# Pair_2.net
KiCad netlist of a schematic drawn in Altium Designer
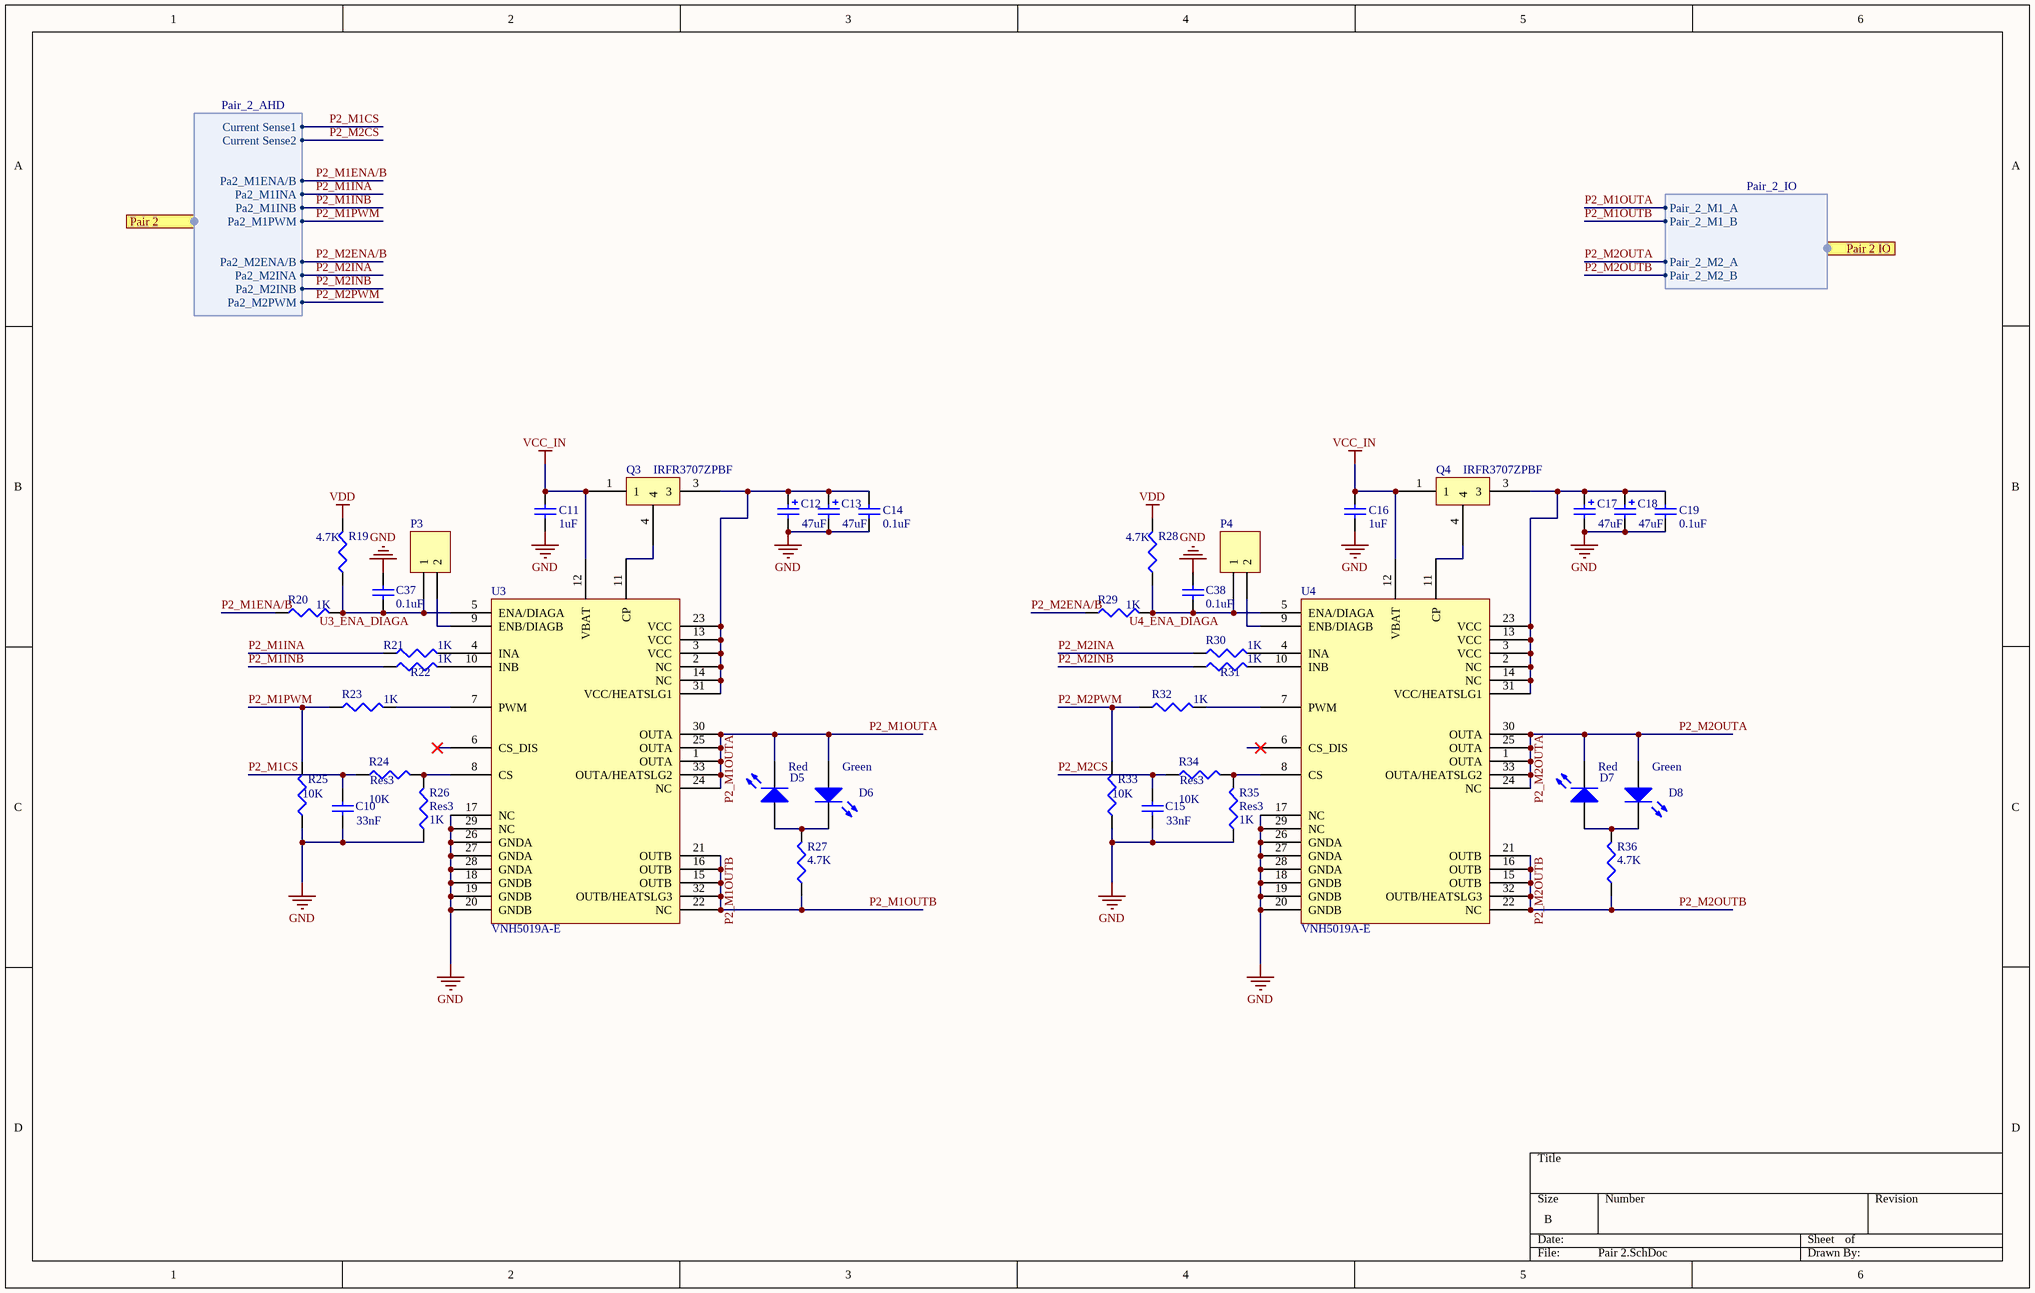
[diagram p0: Pair 2.SchDoc]

(export (version "E")
  (design (tool "Eeschema 10.0.6"))
  (components
    (comp (ref "C10")
      (value "33nF")
      (footprint "1608[0603]")
      (description "Capacitor (Semiconductor SIM Model)")
      (fields (field (name "Comment") "Cap Semi") (field (name "PUBLISHER") "Altium Limited"))
      (libsource (lib "Miscellaneous Devices") (part "Cap Semi"))
    )
    (comp (ref "C11")
      (value "1uF")
      (footprint "1608[0603]")
      (description "Capacitor (Semiconductor SIM Model)")
      (fields (field (name "Comment") "Cap Semi") (field (name "PUBLISHER") "Altium Limited"))
      (libsource (lib "Miscellaneous Devices") (part "Cap Semi"))
    )
    (comp (ref "C12")
      (value "47uF")
      (footprint "CAPPR2-5x6.8")
      (description "Polarized Capacitor (Axial)")
      (fields (field (name "Comment") "Cap Pol2") (field (name "PUBLISHER") "Altium Limited"))
      (libsource (lib "Miscellaneous Devices") (part "Cap Pol2"))
    )
    (comp (ref "C13")
      (value "47uF")
      (footprint "CAPPR2-5x6.8")
      (description "Polarized Capacitor (Axial)")
      (fields (field (name "Comment") "Cap Pol2") (field (name "PUBLISHER") "Altium Limited"))
      (libsource (lib "Miscellaneous Devices") (part "Cap Pol2"))
    )
    (comp (ref "C14")
      (value "0.1uF")
      (footprint "C1206")
      (description "Capacitor (Semiconductor SIM Model)")
      (fields (field (name "Comment") "Cap Semi") (field (name "PUBLISHER") "Altium Limited"))
      (libsource (lib "Miscellaneous Devices") (part "Cap Semi"))
    )
    (comp (ref "C15")
      (value "33nF")
      (footprint "1608[0603]")
      (description "Capacitor (Semiconductor SIM Model)")
      (fields (field (name "Comment") "Cap Semi") (field (name "PUBLISHER") "Altium Limited"))
      (libsource (lib "Miscellaneous Devices") (part "Cap Semi"))
    )
    (comp (ref "C16")
      (value "1uF")
      (footprint "1608[0603]")
      (description "Capacitor (Semiconductor SIM Model)")
      (fields (field (name "Comment") "Cap Semi") (field (name "PUBLISHER") "Altium Limited"))
      (libsource (lib "Miscellaneous Devices") (part "Cap Semi"))
    )
    (comp (ref "C17")
      (value "47uF")
      (footprint "CAPPR2-5x6.8")
      (description "Polarized Capacitor (Axial)")
      (fields (field (name "Comment") "Cap Pol2") (field (name "PUBLISHER") "Altium Limited"))
      (libsource (lib "Miscellaneous Devices") (part "Cap Pol2"))
    )
    (comp (ref "C18")
      (value "47uF")
      (footprint "CAPPR2-5x6.8")
      (description "Polarized Capacitor (Axial)")
      (fields (field (name "Comment") "Cap Pol2") (field (name "PUBLISHER") "Altium Limited"))
      (libsource (lib "Miscellaneous Devices") (part "Cap Pol2"))
    )
    (comp (ref "C19")
      (value "0.1uF")
      (footprint "C1206")
      (description "Capacitor (Semiconductor SIM Model)")
      (fields (field (name "Comment") "Cap Semi") (field (name "PUBLISHER") "Altium Limited"))
      (libsource (lib "Miscellaneous Devices") (part "Cap Semi"))
    )
    (comp (ref "C37")
      (value "0.1uF")
      (footprint "1608[0603]")
      (description "Capacitor (Semiconductor SIM Model)")
      (fields (field (name "Comment") "Cap Semi") (field (name "PUBLISHER") "Altium Limited"))
      (libsource (lib "Miscellaneous Devices") (part "Cap Semi"))
    )
    (comp (ref "C38")
      (value "0.1uF")
      (footprint "1608[0603]")
      (description "Capacitor (Semiconductor SIM Model)")
      (fields (field (name "Comment") "Cap Semi") (field (name "PUBLISHER") "Altium Limited"))
      (libsource (lib "Miscellaneous Devices") (part "Cap Semi"))
    )
    (comp (ref "D5")
      (value "LED2")
      (footprint "3.2X1.6X1.1")
      (description "Typical RED, GREEN, YELLOW, AMBER GaAs LED")
      (fields (field (name "PUBLISHER") "Altium Limited"))
      (libsource (lib "Miscellaneous Devices") (part "LED2"))
    )
    (comp (ref "D6")
      (value "LED2")
      (footprint "3.2X1.6X1.1")
      (description "Typical RED, GREEN, YELLOW, AMBER GaAs LED")
      (fields (field (name "PUBLISHER") "Altium Limited"))
      (libsource (lib "Miscellaneous Devices") (part "LED2"))
    )
    (comp (ref "D7")
      (value "LED2")
      (footprint "3.2X1.6X1.1")
      (description "Typical RED, GREEN, YELLOW, AMBER GaAs LED")
      (fields (field (name "PUBLISHER") "Altium Limited"))
      (libsource (lib "Miscellaneous Devices") (part "LED2"))
    )
    (comp (ref "D8")
      (value "LED2")
      (footprint "3.2X1.6X1.1")
      (description "Typical RED, GREEN, YELLOW, AMBER GaAs LED")
      (fields (field (name "PUBLISHER") "Altium Limited"))
      (libsource (lib "Miscellaneous Devices") (part "LED2"))
    )
    (comp (ref "P3")
      (value "Header 2")
      (footprint "HDR1X2")
      (description "Header, 2-Pin")
      (fields (field (name "PUBLISHER") "Altium Limited"))
      (libsource (lib "Miscellaneous Connectors") (part "Header 2"))
    )
    (comp (ref "P4")
      (value "Header 2")
      (footprint "HDR1X2")
      (description "Header, 2-Pin")
      (fields (field (name "PUBLISHER") "Altium Limited"))
      (libsource (lib "Miscellaneous Connectors") (part "Header 2"))
    )
    (comp (ref "Q3")
      (value "IRFR3707ZPBF")
      (footprint "IRFR3707ZPBF")
      (description "Power FET")
      (libsource (lib "Thruster Shield Part Library") (part "IRFR3707ZPBF"))
    )
    (comp (ref "Q4")
      (value "IRFR3707ZPBF")
      (footprint "IRFR3707ZPBF")
      (description "Power FET")
      (libsource (lib "Thruster Shield Part Library") (part "IRFR3707ZPBF"))
    )
    (comp (ref "R19")
      (value "4.7K")
      (footprint "RESC1608L")
      (description "Resistor")
      (fields (field (name "Comment") "Res3") (field (name "PUBLISHER") "Altium Limited"))
      (libsource (lib "Miscellaneous Devices") (part "Res3"))
    )
    (comp (ref "R20")
      (value "1K")
      (footprint "RESC1608L")
      (description "Resistor")
      (fields (field (name "Comment") "Res3") (field (name "PUBLISHER") "Altium Limited"))
      (libsource (lib "Miscellaneous Devices") (part "Res3"))
    )
    (comp (ref "R21")
      (value "1K")
      (footprint "RESC1608L")
      (description "Resistor")
      (fields (field (name "Comment") "Res3") (field (name "PUBLISHER") "Altium Limited"))
      (libsource (lib "Miscellaneous Devices") (part "Res3"))
    )
    (comp (ref "R22")
      (value "1K")
      (footprint "RESC1608L")
      (description "Resistor")
      (fields (field (name "Comment") "Res3") (field (name "PUBLISHER") "Altium Limited"))
      (libsource (lib "Miscellaneous Devices") (part "Res3"))
    )
    (comp (ref "R23")
      (value "1K")
      (footprint "RESC1608L")
      (description "Resistor")
      (fields (field (name "Comment") "Res3") (field (name "PUBLISHER") "Altium Limited"))
      (libsource (lib "Miscellaneous Devices") (part "Res3"))
    )
    (comp (ref "R24")
      (value "Res3")
      (footprint "RESC1608L")
      (description "Resistor")
      (fields (field (name "ALTIUM_VALUE") "10K") (field (name "PUBLISHER") "Altium Limited"))
      (libsource (lib "Miscellaneous Devices") (part "Res3"))
    )
    (comp (ref "R25")
      (value "10K")
      (footprint "RESC1608L")
      (description "Resistor")
      (fields (field (name "Comment") "Res3") (field (name "PUBLISHER") "Altium Limited"))
      (libsource (lib "Miscellaneous Devices") (part "Res3"))
    )
    (comp (ref "R26")
      (value "Res3")
      (footprint "RESC1608L")
      (description "Resistor")
      (fields (field (name "ALTIUM_VALUE") "1K") (field (name "PUBLISHER") "Altium Limited"))
      (libsource (lib "Miscellaneous Devices") (part "Res3"))
    )
    (comp (ref "R27")
      (value "4.7K")
      (footprint "0805 SMD Resistor")
      (description "Resistor")
      (fields (field (name "Comment") "Res3") (field (name "PUBLISHER") "Altium Limited"))
      (libsource (lib "Miscellaneous Devices") (part "Res3"))
    )
    (comp (ref "R28")
      (value "4.7K")
      (footprint "RESC1608L")
      (description "Resistor")
      (fields (field (name "Comment") "Res3") (field (name "PUBLISHER") "Altium Limited"))
      (libsource (lib "Miscellaneous Devices") (part "Res3"))
    )
    (comp (ref "R29")
      (value "1K")
      (footprint "RESC1608L")
      (description "Resistor")
      (fields (field (name "Comment") "Res3") (field (name "PUBLISHER") "Altium Limited"))
      (libsource (lib "Miscellaneous Devices") (part "Res3"))
    )
    (comp (ref "R30")
      (value "1K")
      (footprint "RESC1608L")
      (description "Resistor")
      (fields (field (name "Comment") "Res3") (field (name "PUBLISHER") "Altium Limited"))
      (libsource (lib "Miscellaneous Devices") (part "Res3"))
    )
    (comp (ref "R31")
      (value "1K")
      (footprint "RESC1608L")
      (description "Resistor")
      (fields (field (name "Comment") "Res3") (field (name "PUBLISHER") "Altium Limited"))
      (libsource (lib "Miscellaneous Devices") (part "Res3"))
    )
    (comp (ref "R32")
      (value "1K")
      (footprint "RESC1608L")
      (description "Resistor")
      (fields (field (name "Comment") "Res3") (field (name "PUBLISHER") "Altium Limited"))
      (libsource (lib "Miscellaneous Devices") (part "Res3"))
    )
    (comp (ref "R33")
      (value "10K")
      (footprint "RESC1608L")
      (description "Resistor")
      (fields (field (name "Comment") "Res3") (field (name "PUBLISHER") "Altium Limited"))
      (libsource (lib "Miscellaneous Devices") (part "Res3"))
    )
    (comp (ref "R34")
      (value "Res3")
      (footprint "RESC1608L")
      (description "Resistor")
      (fields (field (name "ALTIUM_VALUE") "10K") (field (name "PUBLISHER") "Altium Limited"))
      (libsource (lib "Miscellaneous Devices") (part "Res3"))
    )
    (comp (ref "R35")
      (value "Res3")
      (footprint "RESC1608L")
      (description "Resistor")
      (fields (field (name "ALTIUM_VALUE") "1K") (field (name "PUBLISHER") "Altium Limited"))
      (libsource (lib "Miscellaneous Devices") (part "Res3"))
    )
    (comp (ref "R36")
      (value "4.7K")
      (footprint "0805 SMD Resistor")
      (description "Resistor")
      (fields (field (name "Comment") "Res3") (field (name "PUBLISHER") "Altium Limited"))
      (libsource (lib "Miscellaneous Devices") (part "Res3"))
    )
    (comp (ref "U3")
      (value "VNH5019A-E")
      (footprint "VNH5019A-E")
      (description "VNH5019A-E H-Bridge")
      (libsource (lib "Thruster Shield Part Library") (part "VNH5019A-E"))
    )
    (comp (ref "U4")
      (value "VNH5019A-E")
      (footprint "VNH5019A-E")
      (description "VNH5019A-E H-Bridge")
      (libsource (lib "Thruster Shield Part Library") (part "VNH5019A-E"))
    )
  )
  (nets
    (net (code "3") (name "/P2_M1CS") (class "Default")
      (node (ref "C10") (pin "2") (pinfunction "2_2") (pintype "passive"))
      (node (ref "R24") (pin "1") (pinfunction "1_1") (pintype "passive"))
    )
    (net (code "4") (name "/P2_M1ENA{slash}B") (class "Default")
      (node (ref "R20") (pin "1") (pinfunction "1_1") (pintype "passive"))
    )
    (net (code "5") (name "/P2_M1INA") (class "Default")
      (node (ref "R21") (pin "1") (pinfunction "1_1") (pintype "passive"))
    )
    (net (code "6") (name "/P2_M1INB") (class "Default")
      (node (ref "R22") (pin "1") (pinfunction "1_1") (pintype "passive"))
    )
    (net (code "7") (name "/P2_M1OUTA") (class "Default")
      (node (ref "D5") (pin "2") (pinfunction "K_2") (pintype "passive"))
      (node (ref "D6") (pin "1") (pinfunction "A_1") (pintype "passive"))
      (node (ref "U3") (pin "1") (pinfunction "OUTA_1") (pintype "passive"))
      (node (ref "U3") (pin "24") (pinfunction "NC_24") (pintype "passive"))
      (node (ref "U3") (pin "25") (pinfunction "OUTA_25") (pintype "passive"))
      (node (ref "U3") (pin "30") (pinfunction "OUTA_30") (pintype "passive"))
      (node (ref "U3") (pin "33") (pinfunction "OUTA/HEATSLG2_33") (pintype "passive"))
    )
    (net (code "8") (name "/P2_M1OUTB") (class "Default")
      (node (ref "R27") (pin "1") (pinfunction "1_1") (pintype "passive"))
      (node (ref "U3") (pin "15") (pinfunction "OUTB_15") (pintype "passive"))
      (node (ref "U3") (pin "16") (pinfunction "OUTB_16") (pintype "passive"))
      (node (ref "U3") (pin "21") (pinfunction "OUTB_21") (pintype "passive"))
      (node (ref "U3") (pin "22") (pinfunction "NC_22") (pintype "passive"))
      (node (ref "U3") (pin "32") (pinfunction "OUTB/HEATSLG3_32") (pintype "passive"))
    )
    (net (code "9") (name "/P2_M1PWM") (class "Default")
      (node (ref "R23") (pin "1") (pinfunction "1_1") (pintype "passive"))
      (node (ref "R25") (pin "2") (pinfunction "2_2") (pintype "passive"))
    )
    (net (code "10") (name "/P2_M2CS") (class "Default")
      (node (ref "C15") (pin "2") (pinfunction "2_2") (pintype "passive"))
      (node (ref "R34") (pin "1") (pinfunction "1_1") (pintype "passive"))
    )
    (net (code "11") (name "/P2_M2ENA{slash}B") (class "Default")
      (node (ref "R29") (pin "1") (pinfunction "1_1") (pintype "passive"))
    )
    (net (code "12") (name "/P2_M2INA") (class "Default")
      (node (ref "R30") (pin "1") (pinfunction "1_1") (pintype "passive"))
    )
    (net (code "13") (name "/P2_M2INB") (class "Default")
      (node (ref "R31") (pin "1") (pinfunction "1_1") (pintype "passive"))
    )
    (net (code "14") (name "/P2_M2OUTA") (class "Default")
      (node (ref "D7") (pin "2") (pinfunction "K_2") (pintype "passive"))
      (node (ref "D8") (pin "1") (pinfunction "A_1") (pintype "passive"))
      (node (ref "U4") (pin "1") (pinfunction "OUTA_1") (pintype "passive"))
      (node (ref "U4") (pin "24") (pinfunction "NC_24") (pintype "passive"))
      (node (ref "U4") (pin "25") (pinfunction "OUTA_25") (pintype "passive"))
      (node (ref "U4") (pin "30") (pinfunction "OUTA_30") (pintype "passive"))
      (node (ref "U4") (pin "33") (pinfunction "OUTA/HEATSLG2_33") (pintype "passive"))
    )
    (net (code "15") (name "/P2_M2OUTB") (class "Default")
      (node (ref "R36") (pin "1") (pinfunction "1_1") (pintype "passive"))
      (node (ref "U4") (pin "15") (pinfunction "OUTB_15") (pintype "passive"))
      (node (ref "U4") (pin "16") (pinfunction "OUTB_16") (pintype "passive"))
      (node (ref "U4") (pin "21") (pinfunction "OUTB_21") (pintype "passive"))
      (node (ref "U4") (pin "22") (pinfunction "NC_22") (pintype "passive"))
      (node (ref "U4") (pin "32") (pinfunction "OUTB/HEATSLG3_32") (pintype "passive"))
    )
    (net (code "16") (name "/P2_M2PWM") (class "Default")
      (node (ref "R32") (pin "1") (pinfunction "1_1") (pintype "passive"))
      (node (ref "R33") (pin "2") (pinfunction "2_2") (pintype "passive"))
    )
    (net (code "17") (name "/U3_ENA_DIAGA") (class "Default")
      (node (ref "C37") (pin "2") (pinfunction "2_2") (pintype "passive"))
      (node (ref "P3") (pin "1") (pinfunction "1_1") (pintype "passive"))
      (node (ref "R19") (pin "1") (pinfunction "1_1") (pintype "passive"))
      (node (ref "R20") (pin "2") (pinfunction "2_2") (pintype "passive"))
      (node (ref "U3") (pin "5") (pinfunction "ENA/DIAGA_5") (pintype "passive"))
    )
    (net (code "18") (name "/U4_ENA_DIAGA") (class "Default")
      (node (ref "C38") (pin "2") (pinfunction "2_2") (pintype "passive"))
      (node (ref "P4") (pin "1") (pinfunction "1_1") (pintype "passive"))
      (node (ref "R28") (pin "1") (pinfunction "1_1") (pintype "passive"))
      (node (ref "R29") (pin "2") (pinfunction "2_2") (pintype "passive"))
      (node (ref "U4") (pin "5") (pinfunction "ENA/DIAGA_5") (pintype "passive"))
    )
    (net (code "21") (name "GND") (class "Default")
      (node (ref "C10") (pin "1") (pinfunction "1_1") (pintype "passive"))
      (node (ref "C11") (pin "1") (pinfunction "1_1") (pintype "passive"))
      (node (ref "C12") (pin "2") (pinfunction "2_2") (pintype "passive"))
      (node (ref "C13") (pin "2") (pinfunction "2_2") (pintype "passive"))
      (node (ref "C14") (pin "1") (pinfunction "1_1") (pintype "passive"))
      (node (ref "C15") (pin "1") (pinfunction "1_1") (pintype "passive"))
      (node (ref "C16") (pin "1") (pinfunction "1_1") (pintype "passive"))
      (node (ref "C17") (pin "2") (pinfunction "2_2") (pintype "passive"))
      (node (ref "C18") (pin "2") (pinfunction "2_2") (pintype "passive"))
      (node (ref "C19") (pin "1") (pinfunction "1_1") (pintype "passive"))
      (node (ref "C37") (pin "1") (pinfunction "1_1") (pintype "passive"))
      (node (ref "C38") (pin "1") (pinfunction "1_1") (pintype "passive"))
      (node (ref "R25") (pin "1") (pinfunction "1_1") (pintype "passive"))
      (node (ref "R26") (pin "1") (pinfunction "1_1") (pintype "passive"))
      (node (ref "R33") (pin "1") (pinfunction "1_1") (pintype "passive"))
      (node (ref "R35") (pin "1") (pinfunction "1_1") (pintype "passive"))
      (node (ref "U3") (pin "17") (pinfunction "NC_17") (pintype "passive"))
      (node (ref "U3") (pin "18") (pinfunction "GNDB_18") (pintype "passive"))
      (node (ref "U3") (pin "19") (pinfunction "GNDB_19") (pintype "passive"))
      (node (ref "U3") (pin "20") (pinfunction "GNDB_20") (pintype "passive"))
      (node (ref "U3") (pin "26") (pinfunction "GNDA_26") (pintype "passive"))
      (node (ref "U3") (pin "27") (pinfunction "GNDA_27") (pintype "passive"))
      (node (ref "U3") (pin "28") (pinfunction "GNDA_28") (pintype "passive"))
      (node (ref "U3") (pin "29") (pinfunction "NC_29") (pintype "passive"))
      (node (ref "U4") (pin "17") (pinfunction "NC_17") (pintype "passive"))
      (node (ref "U4") (pin "18") (pinfunction "GNDB_18") (pintype "passive"))
      (node (ref "U4") (pin "19") (pinfunction "GNDB_19") (pintype "passive"))
      (node (ref "U4") (pin "20") (pinfunction "GNDB_20") (pintype "passive"))
      (node (ref "U4") (pin "26") (pinfunction "GNDA_26") (pintype "passive"))
      (node (ref "U4") (pin "27") (pinfunction "GNDA_27") (pintype "passive"))
      (node (ref "U4") (pin "28") (pinfunction "GNDA_28") (pintype "passive"))
      (node (ref "U4") (pin "29") (pinfunction "NC_29") (pintype "passive"))
    )
    (net (code "22") (name "Net-(D5-A)") (class "Default")
      (node (ref "D5") (pin "1") (pinfunction "A_1") (pintype "passive"))
      (node (ref "D6") (pin "2") (pinfunction "K_2") (pintype "passive"))
      (node (ref "R27") (pin "2") (pinfunction "2_2") (pintype "passive"))
    )
    (net (code "23") (name "Net-(D7-A)") (class "Default")
      (node (ref "D7") (pin "1") (pinfunction "A_1") (pintype "passive"))
      (node (ref "D8") (pin "2") (pinfunction "K_2") (pintype "passive"))
      (node (ref "R36") (pin "2") (pinfunction "2_2") (pintype "passive"))
    )
    (net (code "24") (name "Net-(U3-CP)") (class "Default")
      (node (ref "Q3") (pin "4") (pinfunction "4_4") (pintype "passive"))
      (node (ref "U3") (pin "11") (pinfunction "CP_11") (pintype "passive"))
    )
    (net (code "25") (name "Net-(U3-CS)") (class "Default")
      (node (ref "R24") (pin "2") (pinfunction "2_2") (pintype "passive"))
      (node (ref "R26") (pin "2") (pinfunction "2_2") (pintype "passive"))
      (node (ref "U3") (pin "8") (pinfunction "CS_8") (pintype "passive"))
    )
    (net (code "26") (name "Net-(U3-ENB{slash}DIAGB)") (class "Default")
      (node (ref "P3") (pin "2") (pinfunction "2_2") (pintype "passive"))
      (node (ref "U3") (pin "9") (pinfunction "ENB/DIAGB_9") (pintype "passive"))
    )
    (net (code "27") (name "Net-(U3-INA)") (class "Default")
      (node (ref "R21") (pin "2") (pinfunction "2_2") (pintype "passive"))
      (node (ref "U3") (pin "4") (pinfunction "INA_4") (pintype "passive"))
    )
    (net (code "28") (name "Net-(U3-INB)") (class "Default")
      (node (ref "R22") (pin "2") (pinfunction "2_2") (pintype "passive"))
      (node (ref "U3") (pin "10") (pinfunction "INB_10") (pintype "passive"))
    )
    (net (code "29") (name "Net-(U3-PWM)") (class "Default")
      (node (ref "R23") (pin "2") (pinfunction "2_2") (pintype "passive"))
      (node (ref "U3") (pin "7") (pinfunction "PWM_7") (pintype "passive"))
    )
    (net (code "30") (name "Net-(U3-VCC{slash}HEATSLG1)") (class "Default")
      (node (ref "C12") (pin "1") (pinfunction "1_1") (pintype "passive"))
      (node (ref "C13") (pin "1") (pinfunction "1_1") (pintype "passive"))
      (node (ref "C14") (pin "2") (pinfunction "2_2") (pintype "passive"))
      (node (ref "Q3") (pin "3") (pinfunction "3_3") (pintype "passive"))
      (node (ref "U3") (pin "13") (pinfunction "VCC_13") (pintype "passive"))
      (node (ref "U3") (pin "14") (pinfunction "NC_14") (pintype "passive"))
      (node (ref "U3") (pin "2") (pinfunction "NC_2") (pintype "passive"))
      (node (ref "U3") (pin "23") (pinfunction "VCC_23") (pintype "passive"))
      (node (ref "U3") (pin "3") (pinfunction "VCC_3") (pintype "passive"))
      (node (ref "U3") (pin "31") (pinfunction "VCC/HEATSLG1_31") (pintype "passive"))
    )
    (net (code "31") (name "Net-(U4-CP)") (class "Default")
      (node (ref "Q4") (pin "4") (pinfunction "4_4") (pintype "passive"))
      (node (ref "U4") (pin "11") (pinfunction "CP_11") (pintype "passive"))
    )
    (net (code "32") (name "Net-(U4-CS)") (class "Default")
      (node (ref "R34") (pin "2") (pinfunction "2_2") (pintype "passive"))
      (node (ref "R35") (pin "2") (pinfunction "2_2") (pintype "passive"))
      (node (ref "U4") (pin "8") (pinfunction "CS_8") (pintype "passive"))
    )
    (net (code "33") (name "Net-(U4-ENB{slash}DIAGB)") (class "Default")
      (node (ref "P4") (pin "2") (pinfunction "2_2") (pintype "passive"))
      (node (ref "U4") (pin "9") (pinfunction "ENB/DIAGB_9") (pintype "passive"))
    )
    (net (code "34") (name "Net-(U4-INA)") (class "Default")
      (node (ref "R30") (pin "2") (pinfunction "2_2") (pintype "passive"))
      (node (ref "U4") (pin "4") (pinfunction "INA_4") (pintype "passive"))
    )
    (net (code "35") (name "Net-(U4-INB)") (class "Default")
      (node (ref "R31") (pin "2") (pinfunction "2_2") (pintype "passive"))
      (node (ref "U4") (pin "10") (pinfunction "INB_10") (pintype "passive"))
    )
    (net (code "36") (name "Net-(U4-PWM)") (class "Default")
      (node (ref "R32") (pin "2") (pinfunction "2_2") (pintype "passive"))
      (node (ref "U4") (pin "7") (pinfunction "PWM_7") (pintype "passive"))
    )
    (net (code "37") (name "Net-(U4-VCC{slash}HEATSLG1)") (class "Default")
      (node (ref "C17") (pin "1") (pinfunction "1_1") (pintype "passive"))
      (node (ref "C18") (pin "1") (pinfunction "1_1") (pintype "passive"))
      (node (ref "C19") (pin "2") (pinfunction "2_2") (pintype "passive"))
      (node (ref "Q4") (pin "3") (pinfunction "3_3") (pintype "passive"))
      (node (ref "U4") (pin "13") (pinfunction "VCC_13") (pintype "passive"))
      (node (ref "U4") (pin "14") (pinfunction "NC_14") (pintype "passive"))
      (node (ref "U4") (pin "2") (pinfunction "NC_2") (pintype "passive"))
      (node (ref "U4") (pin "23") (pinfunction "VCC_23") (pintype "passive"))
      (node (ref "U4") (pin "3") (pinfunction "VCC_3") (pintype "passive"))
      (node (ref "U4") (pin "31") (pinfunction "VCC/HEATSLG1_31") (pintype "passive"))
    )
    (net (code "38") (name "VCC_IN") (class "Default")
      (node (ref "C11") (pin "2") (pinfunction "2_2") (pintype "passive"))
      (node (ref "C16") (pin "2") (pinfunction "2_2") (pintype "passive"))
      (node (ref "Q3") (pin "1") (pinfunction "1_1") (pintype "passive"))
      (node (ref "Q4") (pin "1") (pinfunction "1_1") (pintype "passive"))
      (node (ref "U3") (pin "12") (pinfunction "VBAT_12") (pintype "passive"))
      (node (ref "U4") (pin "12") (pinfunction "VBAT_12") (pintype "passive"))
    )
    (net (code "39") (name "VDD") (class "Default")
      (node (ref "R19") (pin "2") (pinfunction "2_2") (pintype "passive"))
      (node (ref "R28") (pin "2") (pinfunction "2_2") (pintype "passive"))
    )
    (net (code "40") (name "unconnected-(U3-CS_DIS-Pad6)") (class "Default")
      (node (ref "U3") (pin "6") (pinfunction "CS_DIS_6") (pintype "passive+no_connect"))
    )
    (net (code "41") (name "unconnected-(U4-CS_DIS-Pad6)") (class "Default")
      (node (ref "U4") (pin "6") (pinfunction "CS_DIS_6") (pintype "passive+no_connect"))
    )
  )
)
